# 07_LMS7002M_Power.net
KiCad netlist of a schematic drawn in Altium Designer
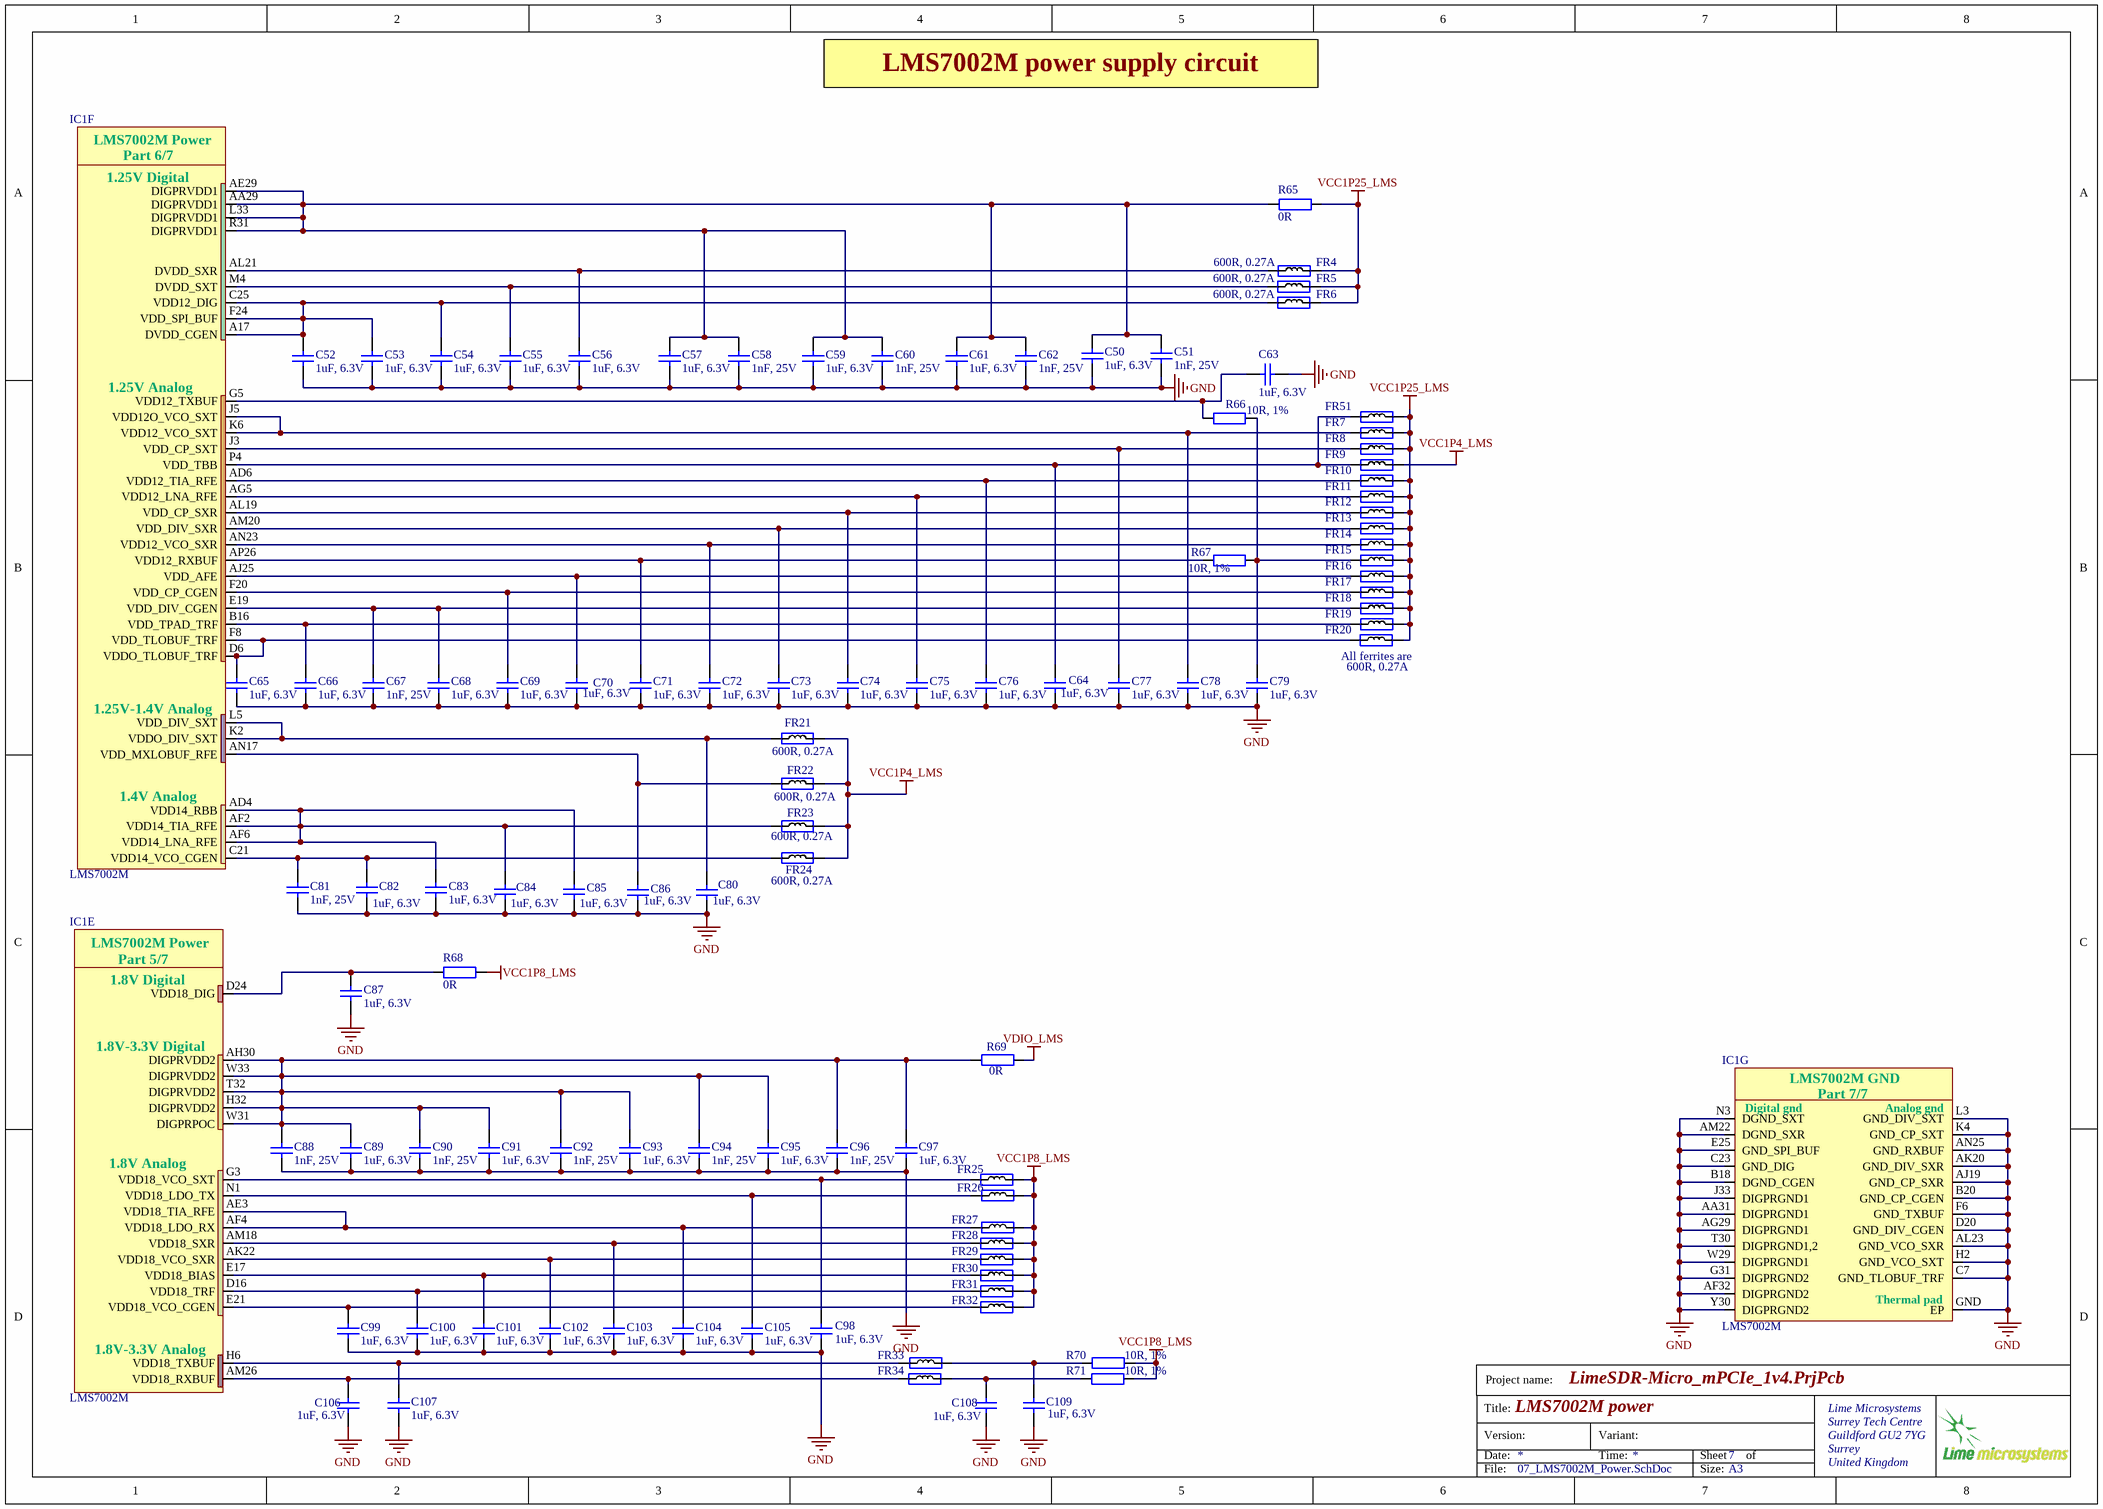
[diagram p0: 07_LMS7002M_Power.SchDoc]

(export (version "E")
  (design (tool "Eeschema 10.0.6"))
  (components
    (comp (ref "C50")
      (value "1uF, 6.3V")
      (footprint "CAP0201")
      (fields (field (name "TOLERANCE") "±20%") (field (name "MANUFACTURER") "TDK Corporation"))
      (libsource (lib "LimeMicroAltiumLib_schLib") (part "Cap_0402"))
    )
    (comp (ref "C51")
      (value "1nF, 25V")
      (footprint "CAP0201")
      (fields (field (name "TOLERANCE") "±10%") (field (name "MANUFACTURER") "TDK Corporation"))
      (libsource (lib "LimeMicroAltiumLib_schLib") (part "Cap_0402"))
    )
    (comp (ref "C52")
      (value "1uF, 6.3V")
      (footprint "CAP0201")
      (fields (field (name "TOLERANCE") "±20%") (field (name "MANUFACTURER") "TDK Corporation"))
      (libsource (lib "LimeMicroAltiumLib_schLib") (part "Cap_0402"))
    )
    (comp (ref "C53")
      (value "1uF, 6.3V")
      (footprint "CAP0201")
      (fields (field (name "TOLERANCE") "±20%") (field (name "MANUFACTURER") "TDK Corporation"))
      (libsource (lib "LimeMicroAltiumLib_schLib") (part "Cap_0402"))
    )
    (comp (ref "C54")
      (value "1uF, 6.3V")
      (footprint "CAP0201")
      (fields (field (name "TOLERANCE") "±20%") (field (name "MANUFACTURER") "TDK Corporation"))
      (libsource (lib "LimeMicroAltiumLib_schLib") (part "Cap_0402"))
    )
    (comp (ref "C55")
      (value "1uF, 6.3V")
      (footprint "CAP0201")
      (fields (field (name "TOLERANCE") "±20%") (field (name "MANUFACTURER") "TDK Corporation"))
      (libsource (lib "LimeMicroAltiumLib_schLib") (part "Cap_0402"))
    )
    (comp (ref "C56")
      (value "1uF, 6.3V")
      (footprint "CAP0201")
      (fields (field (name "TOLERANCE") "±20%") (field (name "MANUFACTURER") "TDK Corporation"))
      (libsource (lib "LimeMicroAltiumLib_schLib") (part "Cap_0402"))
    )
    (comp (ref "C57")
      (value "1uF, 6.3V")
      (footprint "CAP0201")
      (fields (field (name "TOLERANCE") "±20%") (field (name "MANUFACTURER") "TDK Corporation"))
      (libsource (lib "LimeMicroAltiumLib_schLib") (part "Cap_0402"))
    )
    (comp (ref "C58")
      (value "1nF, 25V")
      (footprint "CAP0201")
      (fields (field (name "TOLERANCE") "±10%") (field (name "MANUFACTURER") "TDK Corporation"))
      (libsource (lib "LimeMicroAltiumLib_schLib") (part "Cap_0402"))
    )
    (comp (ref "C59")
      (value "1uF, 6.3V")
      (footprint "CAP0201")
      (fields (field (name "TOLERANCE") "±20%") (field (name "MANUFACTURER") "TDK Corporation"))
      (libsource (lib "LimeMicroAltiumLib_schLib") (part "Cap_0402"))
    )
    (comp (ref "C60")
      (value "1nF, 25V")
      (footprint "CAP0201")
      (fields (field (name "TOLERANCE") "±10%") (field (name "MANUFACTURER") "TDK Corporation"))
      (libsource (lib "LimeMicroAltiumLib_schLib") (part "Cap_0402"))
    )
    (comp (ref "C61")
      (value "1uF, 6.3V")
      (footprint "CAP0201")
      (fields (field (name "TOLERANCE") "±20%") (field (name "MANUFACTURER") "TDK Corporation"))
      (libsource (lib "LimeMicroAltiumLib_schLib") (part "Cap_0402"))
    )
    (comp (ref "C62")
      (value "1nF, 25V")
      (footprint "CAP0201")
      (fields (field (name "TOLERANCE") "±10%") (field (name "MANUFACTURER") "TDK Corporation"))
      (libsource (lib "LimeMicroAltiumLib_schLib") (part "Cap_0402"))
    )
    (comp (ref "C63")
      (value "1uF, 6.3V")
      (footprint "CAP0201")
      (fields (field (name "TOLERANCE") "±20%") (field (name "MANUFACTURER") "TDK Corporation"))
      (libsource (lib "LimeMicroAltiumLib_schLib") (part "Cap_0402"))
    )
    (comp (ref "C64")
      (value "1uF, 6.3V")
      (footprint "CAP0201")
      (fields (field (name "TOLERANCE") "±20%") (field (name "MANUFACTURER") "TDK Corporation"))
      (libsource (lib "LimeMicroAltiumLib_schLib") (part "Cap_0402"))
    )
    (comp (ref "C65")
      (value "1uF, 6.3V")
      (footprint "CAP0201")
      (fields (field (name "TOLERANCE") "±20%") (field (name "MANUFACTURER") "TDK Corporation"))
      (libsource (lib "LimeMicroAltiumLib_schLib") (part "Cap_0402"))
    )
    (comp (ref "C66")
      (value "1uF, 6.3V")
      (footprint "CAP0201")
      (fields (field (name "TOLERANCE") "±20%") (field (name "MANUFACTURER") "TDK Corporation"))
      (libsource (lib "LimeMicroAltiumLib_schLib") (part "Cap_0402"))
    )
    (comp (ref "C67")
      (value "1nF, 25V")
      (footprint "CAP0201")
      (fields (field (name "TOLERANCE") "±10%") (field (name "MANUFACTURER") "TDK Corporation"))
      (libsource (lib "LimeMicroAltiumLib_schLib") (part "Cap_0402"))
    )
    (comp (ref "C68")
      (value "1uF, 6.3V")
      (footprint "CAP0201")
      (fields (field (name "TOLERANCE") "±20%") (field (name "MANUFACTURER") "TDK Corporation"))
      (libsource (lib "LimeMicroAltiumLib_schLib") (part "Cap_0402"))
    )
    (comp (ref "C69")
      (value "1uF, 6.3V")
      (footprint "CAP0201")
      (fields (field (name "TOLERANCE") "±20%") (field (name "MANUFACTURER") "TDK Corporation"))
      (libsource (lib "LimeMicroAltiumLib_schLib") (part "Cap_0402"))
    )
    (comp (ref "C70")
      (value "1uF, 6.3V")
      (footprint "CAP0201")
      (fields (field (name "TOLERANCE") "±20%") (field (name "MANUFACTURER") "TDK Corporation"))
      (libsource (lib "LimeMicroAltiumLib_schLib") (part "Cap_0402"))
    )
    (comp (ref "C71")
      (value "1uF, 6.3V")
      (footprint "CAP0201")
      (fields (field (name "TOLERANCE") "±20%") (field (name "MANUFACTURER") "TDK Corporation"))
      (libsource (lib "LimeMicroAltiumLib_schLib") (part "Cap_0402"))
    )
    (comp (ref "C72")
      (value "1uF, 6.3V")
      (footprint "CAP0201")
      (fields (field (name "TOLERANCE") "±20%") (field (name "MANUFACTURER") "TDK Corporation"))
      (libsource (lib "LimeMicroAltiumLib_schLib") (part "Cap_0402"))
    )
    (comp (ref "C73")
      (value "1uF, 6.3V")
      (footprint "CAP0201")
      (fields (field (name "TOLERANCE") "±20%") (field (name "MANUFACTURER") "TDK Corporation"))
      (libsource (lib "LimeMicroAltiumLib_schLib") (part "Cap_0402"))
    )
    (comp (ref "C74")
      (value "1uF, 6.3V")
      (footprint "CAP0201")
      (fields (field (name "TOLERANCE") "±20%") (field (name "MANUFACTURER") "TDK Corporation"))
      (libsource (lib "LimeMicroAltiumLib_schLib") (part "Cap_0402"))
    )
    (comp (ref "C75")
      (value "1uF, 6.3V")
      (footprint "CAP0201")
      (fields (field (name "TOLERANCE") "±20%") (field (name "MANUFACTURER") "TDK Corporation"))
      (libsource (lib "LimeMicroAltiumLib_schLib") (part "Cap_0402"))
    )
    (comp (ref "C76")
      (value "1uF, 6.3V")
      (footprint "CAP0201")
      (fields (field (name "TOLERANCE") "±20%") (field (name "MANUFACTURER") "TDK Corporation"))
      (libsource (lib "LimeMicroAltiumLib_schLib") (part "Cap_0402"))
    )
    (comp (ref "C77")
      (value "1uF, 6.3V")
      (footprint "CAP0201")
      (fields (field (name "TOLERANCE") "±20%") (field (name "MANUFACTURER") "TDK Corporation"))
      (libsource (lib "LimeMicroAltiumLib_schLib") (part "Cap_0402"))
    )
    (comp (ref "C78")
      (value "1uF, 6.3V")
      (footprint "CAP0201")
      (fields (field (name "TOLERANCE") "±20%") (field (name "MANUFACTURER") "TDK Corporation"))
      (libsource (lib "LimeMicroAltiumLib_schLib") (part "Cap_0402"))
    )
    (comp (ref "C79")
      (value "1uF, 6.3V")
      (footprint "CAP0201")
      (fields (field (name "TOLERANCE") "±20%") (field (name "MANUFACTURER") "TDK Corporation"))
      (libsource (lib "LimeMicroAltiumLib_schLib") (part "Cap_0402"))
    )
    (comp (ref "C80")
      (value "1uF, 6.3V")
      (footprint "CAP0201")
      (fields (field (name "TOLERANCE") "±20%") (field (name "MANUFACTURER") "TDK Corporation"))
      (libsource (lib "LimeMicroAltiumLib_schLib") (part "Cap_0402"))
    )
    (comp (ref "C81")
      (value "1nF, 25V")
      (footprint "CAP0201")
      (fields (field (name "TOLERANCE") "±10%") (field (name "MANUFACTURER") "TDK Corporation"))
      (libsource (lib "LimeMicroAltiumLib_schLib") (part "Cap_0402"))
    )
    (comp (ref "C82")
      (value "1uF, 6.3V")
      (footprint "CAP0201")
      (fields (field (name "TOLERANCE") "±20%") (field (name "MANUFACTURER") "TDK Corporation"))
      (libsource (lib "LimeMicroAltiumLib_schLib") (part "Cap_0402"))
    )
    (comp (ref "C83")
      (value "1uF, 6.3V")
      (footprint "CAP0201")
      (fields (field (name "TOLERANCE") "±20%") (field (name "MANUFACTURER") "TDK Corporation"))
      (libsource (lib "LimeMicroAltiumLib_schLib") (part "Cap_0402"))
    )
    (comp (ref "C84")
      (value "1uF, 6.3V")
      (footprint "CAP0201")
      (fields (field (name "TOLERANCE") "±20%") (field (name "MANUFACTURER") "TDK Corporation"))
      (libsource (lib "LimeMicroAltiumLib_schLib") (part "Cap_0402"))
    )
    (comp (ref "C85")
      (value "1uF, 6.3V")
      (footprint "CAP0201")
      (fields (field (name "TOLERANCE") "±20%") (field (name "MANUFACTURER") "TDK Corporation"))
      (libsource (lib "LimeMicroAltiumLib_schLib") (part "Cap_0402"))
    )
    (comp (ref "C86")
      (value "1uF, 6.3V")
      (footprint "CAP0201")
      (fields (field (name "TOLERANCE") "±20%") (field (name "MANUFACTURER") "TDK Corporation"))
      (libsource (lib "LimeMicroAltiumLib_schLib") (part "Cap_0402"))
    )
    (comp (ref "C87")
      (value "1uF, 6.3V")
      (footprint "CAP0201")
      (fields (field (name "TOLERANCE") "±20%") (field (name "MANUFACTURER") "TDK Corporation"))
      (libsource (lib "LimeMicroAltiumLib_schLib") (part "Cap_0402"))
    )
    (comp (ref "C88")
      (value "1nF, 25V")
      (footprint "CAP0201")
      (fields (field (name "TOLERANCE") "±10%") (field (name "MANUFACTURER") "TDK Corporation"))
      (libsource (lib "LimeMicroAltiumLib_schLib") (part "Cap_0402"))
    )
    (comp (ref "C89")
      (value "1uF, 6.3V")
      (footprint "CAP0201")
      (fields (field (name "TOLERANCE") "±20%") (field (name "MANUFACTURER") "TDK Corporation"))
      (libsource (lib "LimeMicroAltiumLib_schLib") (part "Cap_0402"))
    )
    (comp (ref "C90")
      (value "1nF, 25V")
      (footprint "CAP0201")
      (fields (field (name "TOLERANCE") "±10%") (field (name "MANUFACTURER") "TDK Corporation"))
      (libsource (lib "LimeMicroAltiumLib_schLib") (part "Cap_0402"))
    )
    (comp (ref "C91")
      (value "1uF, 6.3V")
      (footprint "CAP0201")
      (fields (field (name "TOLERANCE") "±20%") (field (name "MANUFACTURER") "TDK Corporation"))
      (libsource (lib "LimeMicroAltiumLib_schLib") (part "Cap_0402"))
    )
    (comp (ref "C92")
      (value "1nF, 25V")
      (footprint "CAP0201")
      (fields (field (name "TOLERANCE") "±10%") (field (name "MANUFACTURER") "TDK Corporation"))
      (libsource (lib "LimeMicroAltiumLib_schLib") (part "Cap_0402"))
    )
    (comp (ref "C93")
      (value "1uF, 6.3V")
      (footprint "CAP0201")
      (fields (field (name "TOLERANCE") "±20%") (field (name "MANUFACTURER") "TDK Corporation"))
      (libsource (lib "LimeMicroAltiumLib_schLib") (part "Cap_0402"))
    )
    (comp (ref "C94")
      (value "1nF, 25V")
      (footprint "CAP0201")
      (fields (field (name "TOLERANCE") "±10%") (field (name "MANUFACTURER") "TDK Corporation"))
      (libsource (lib "LimeMicroAltiumLib_schLib") (part "Cap_0402"))
    )
    (comp (ref "C95")
      (value "1uF, 6.3V")
      (footprint "CAP0201")
      (fields (field (name "TOLERANCE") "±20%") (field (name "MANUFACTURER") "TDK Corporation"))
      (libsource (lib "LimeMicroAltiumLib_schLib") (part "Cap_0402"))
    )
    (comp (ref "C96")
      (value "1nF, 25V")
      (footprint "CAP0201")
      (fields (field (name "TOLERANCE") "±10%") (field (name "MANUFACTURER") "TDK Corporation"))
      (libsource (lib "LimeMicroAltiumLib_schLib") (part "Cap_0402"))
    )
    (comp (ref "C97")
      (value "1uF, 6.3V")
      (footprint "CAP0201")
      (fields (field (name "TOLERANCE") "±20%") (field (name "MANUFACTURER") "TDK Corporation"))
      (libsource (lib "LimeMicroAltiumLib_schLib") (part "Cap_0402"))
    )
    (comp (ref "C98")
      (value "1uF, 6.3V")
      (footprint "CAP0201")
      (fields (field (name "TOLERANCE") "±20%") (field (name "MANUFACTURER") "TDK Corporation"))
      (libsource (lib "LimeMicroAltiumLib_schLib") (part "Cap_0402"))
    )
    (comp (ref "C99")
      (value "1uF, 6.3V")
      (footprint "CAP0201")
      (fields (field (name "TOLERANCE") "±20%") (field (name "MANUFACTURER") "TDK Corporation"))
      (libsource (lib "LimeMicroAltiumLib_schLib") (part "Cap_0402"))
    )
    (comp (ref "C100")
      (value "1uF, 6.3V")
      (footprint "CAP0201")
      (fields (field (name "TOLERANCE") "±20%") (field (name "MANUFACTURER") "TDK Corporation"))
      (libsource (lib "LimeMicroAltiumLib_schLib") (part "Cap_0402"))
    )
    (comp (ref "C101")
      (value "1uF, 6.3V")
      (footprint "CAP0201")
      (fields (field (name "TOLERANCE") "±20%") (field (name "MANUFACTURER") "TDK Corporation"))
      (libsource (lib "LimeMicroAltiumLib_schLib") (part "Cap_0402"))
    )
    (comp (ref "C102")
      (value "1uF, 6.3V")
      (footprint "CAP0201")
      (fields (field (name "TOLERANCE") "±20%") (field (name "MANUFACTURER") "TDK Corporation"))
      (libsource (lib "LimeMicroAltiumLib_schLib") (part "Cap_0402"))
    )
    (comp (ref "C103")
      (value "1uF, 6.3V")
      (footprint "CAP0201")
      (fields (field (name "TOLERANCE") "±20%") (field (name "MANUFACTURER") "TDK Corporation"))
      (libsource (lib "LimeMicroAltiumLib_schLib") (part "Cap_0402"))
    )
    (comp (ref "C104")
      (value "1uF, 6.3V")
      (footprint "CAP0201")
      (fields (field (name "TOLERANCE") "±20%") (field (name "MANUFACTURER") "TDK Corporation"))
      (libsource (lib "LimeMicroAltiumLib_schLib") (part "Cap_0402"))
    )
    (comp (ref "C105")
      (value "1uF, 6.3V")
      (footprint "CAP0201")
      (fields (field (name "TOLERANCE") "±20%") (field (name "MANUFACTURER") "TDK Corporation"))
      (libsource (lib "LimeMicroAltiumLib_schLib") (part "Cap_0402"))
    )
    (comp (ref "C106")
      (value "1uF, 6.3V")
      (footprint "CAP0201")
      (fields (field (name "TOLERANCE") "±20%") (field (name "MANUFACTURER") "TDK Corporation"))
      (libsource (lib "LimeMicroAltiumLib_schLib") (part "Cap_0402"))
    )
    (comp (ref "C107")
      (value "1uF, 6.3V")
      (footprint "CAP0201")
      (fields (field (name "TOLERANCE") "±20%") (field (name "MANUFACTURER") "TDK Corporation"))
      (libsource (lib "LimeMicroAltiumLib_schLib") (part "Cap_0402"))
    )
    (comp (ref "C108")
      (value "1uF, 6.3V")
      (footprint "CAP0201")
      (fields (field (name "TOLERANCE") "±20%") (field (name "MANUFACTURER") "TDK Corporation"))
      (libsource (lib "LimeMicroAltiumLib_schLib") (part "Cap_0402"))
    )
    (comp (ref "C109")
      (value "1uF, 6.3V")
      (footprint "CAP0201")
      (fields (field (name "TOLERANCE") "±20%") (field (name "MANUFACTURER") "TDK Corporation"))
      (libsource (lib "LimeMicroAltiumLib_schLib") (part "Cap_0402"))
    )
    (comp (ref "FR4")
      (value "600R, 0.27A")
      (footprint "RES0201")
      (fields (field (name "MANUFACTURER") "Taiyo Yuden"))
      (libsource (lib "LimeMicroAltiumLib_schLib") (part "Ferrite"))
    )
    (comp (ref "FR5")
      (value "600R, 0.27A")
      (footprint "RES0201")
      (fields (field (name "MANUFACTURER") "Taiyo Yuden"))
      (libsource (lib "LimeMicroAltiumLib_schLib") (part "Ferrite"))
    )
    (comp (ref "FR6")
      (value "600R, 0.27A")
      (footprint "RES0201")
      (fields (field (name "MANUFACTURER") "Taiyo Yuden"))
      (libsource (lib "LimeMicroAltiumLib_schLib") (part "Ferrite"))
    )
    (comp (ref "FR7")
      (value "600R, 0.27A")
      (footprint "RES0201")
      (fields (field (name "MANUFACTURER") "Taiyo Yuden"))
      (libsource (lib "LimeMicroAltiumLib_schLib") (part "Ferrite"))
    )
    (comp (ref "FR8")
      (value "600R, 0.27A")
      (footprint "RES0201")
      (fields (field (name "MANUFACTURER") "Taiyo Yuden"))
      (libsource (lib "LimeMicroAltiumLib_schLib") (part "Ferrite"))
    )
    (comp (ref "FR9")
      (value "600R, 0.27A")
      (footprint "RES0201")
      (fields (field (name "MANUFACTURER") "Taiyo Yuden"))
      (libsource (lib "LimeMicroAltiumLib_schLib") (part "Ferrite"))
    )
    (comp (ref "FR10")
      (value "600R, 0.27A")
      (footprint "RES0201")
      (fields (field (name "MANUFACTURER") "Taiyo Yuden"))
      (libsource (lib "LimeMicroAltiumLib_schLib") (part "Ferrite"))
    )
    (comp (ref "FR11")
      (value "600R, 0.27A")
      (footprint "RES0201")
      (fields (field (name "MANUFACTURER") "Taiyo Yuden"))
      (libsource (lib "LimeMicroAltiumLib_schLib") (part "Ferrite"))
    )
    (comp (ref "FR12")
      (value "600R, 0.27A")
      (footprint "RES0201")
      (fields (field (name "MANUFACTURER") "Taiyo Yuden"))
      (libsource (lib "LimeMicroAltiumLib_schLib") (part "Ferrite"))
    )
    (comp (ref "FR13")
      (value "600R, 0.27A")
      (footprint "RES0201")
      (fields (field (name "MANUFACTURER") "Taiyo Yuden"))
      (libsource (lib "LimeMicroAltiumLib_schLib") (part "Ferrite"))
    )
    (comp (ref "FR14")
      (value "600R, 0.27A")
      (footprint "RES0201")
      (fields (field (name "MANUFACTURER") "Taiyo Yuden"))
      (libsource (lib "LimeMicroAltiumLib_schLib") (part "Ferrite"))
    )
    (comp (ref "FR15")
      (value "600R, 0.27A")
      (footprint "RES0201")
      (fields (field (name "MANUFACTURER") "Taiyo Yuden"))
      (libsource (lib "LimeMicroAltiumLib_schLib") (part "Ferrite"))
    )
    (comp (ref "FR16")
      (value "600R, 0.27A")
      (footprint "RES0201")
      (fields (field (name "MANUFACTURER") "Taiyo Yuden"))
      (libsource (lib "LimeMicroAltiumLib_schLib") (part "Ferrite"))
    )
    (comp (ref "FR17")
      (value "600R, 0.27A")
      (footprint "RES0201")
      (fields (field (name "MANUFACTURER") "Taiyo Yuden"))
      (libsource (lib "LimeMicroAltiumLib_schLib") (part "Ferrite"))
    )
    (comp (ref "FR18")
      (value "600R, 0.27A")
      (footprint "RES0201")
      (fields (field (name "MANUFACTURER") "Taiyo Yuden"))
      (libsource (lib "LimeMicroAltiumLib_schLib") (part "Ferrite"))
    )
    (comp (ref "FR19")
      (value "600R, 0.27A")
      (footprint "RES0201")
      (fields (field (name "MANUFACTURER") "Taiyo Yuden"))
      (libsource (lib "LimeMicroAltiumLib_schLib") (part "Ferrite"))
    )
    (comp (ref "FR20")
      (value "600R, 0.27A")
      (footprint "RES0201")
      (fields (field (name "MANUFACTURER") "Taiyo Yuden"))
      (libsource (lib "LimeMicroAltiumLib_schLib") (part "Ferrite"))
    )
    (comp (ref "FR21")
      (value "600R, 0.27A")
      (footprint "RES0201")
      (fields (field (name "MANUFACTURER") "Taiyo Yuden"))
      (libsource (lib "LimeMicroAltiumLib_schLib") (part "Ferrite"))
    )
    (comp (ref "FR22")
      (value "600R, 0.27A")
      (footprint "RES0201")
      (fields (field (name "MANUFACTURER") "Taiyo Yuden"))
      (libsource (lib "LimeMicroAltiumLib_schLib") (part "Ferrite"))
    )
    (comp (ref "FR23")
      (value "600R, 0.27A")
      (footprint "RES0201")
      (fields (field (name "MANUFACTURER") "Taiyo Yuden"))
      (libsource (lib "LimeMicroAltiumLib_schLib") (part "Ferrite"))
    )
    (comp (ref "FR24")
      (value "600R, 0.27A")
      (footprint "RES0201")
      (fields (field (name "MANUFACTURER") "Taiyo Yuden"))
      (libsource (lib "LimeMicroAltiumLib_schLib") (part "Ferrite"))
    )
    (comp (ref "FR25")
      (value "600R, 0.27A")
      (footprint "RES0201")
      (fields (field (name "MANUFACTURER") "Taiyo Yuden"))
      (libsource (lib "LimeMicroAltiumLib_schLib") (part "Ferrite"))
    )
    (comp (ref "FR26")
      (value "600R, 0.27A")
      (footprint "RES0201")
      (fields (field (name "MANUFACTURER") "Taiyo Yuden"))
      (libsource (lib "") (part "Ferrite_1"))
    )
    (comp (ref "FR27")
      (value "600R, 0.27A")
      (footprint "RES0201")
      (fields (field (name "MANUFACTURER") "Taiyo Yuden"))
      (libsource (lib "") (part "Ferrite_1"))
    )
    (comp (ref "FR28")
      (value "600R, 0.27A")
      (footprint "RES0201")
      (fields (field (name "MANUFACTURER") "Taiyo Yuden"))
      (libsource (lib "LimeMicroAltiumLib_schLib") (part "Ferrite"))
    )
    (comp (ref "FR29")
      (value "600R, 0.27A")
      (footprint "RES0201")
      (fields (field (name "MANUFACTURER") "Taiyo Yuden"))
      (libsource (lib "LimeMicroAltiumLib_schLib") (part "Ferrite"))
    )
    (comp (ref "FR30")
      (value "600R, 0.27A")
      (footprint "RES0201")
      (fields (field (name "MANUFACTURER") "Taiyo Yuden"))
      (libsource (lib "LimeMicroAltiumLib_schLib") (part "Ferrite"))
    )
    (comp (ref "FR31")
      (value "600R, 0.27A")
      (footprint "RES0201")
      (fields (field (name "MANUFACTURER") "Taiyo Yuden"))
      (libsource (lib "LimeMicroAltiumLib_schLib") (part "Ferrite"))
    )
    (comp (ref "FR32")
      (value "600R, 0.27A")
      (footprint "RES0201")
      (fields (field (name "MANUFACTURER") "Taiyo Yuden"))
      (libsource (lib "LimeMicroAltiumLib_schLib") (part "Ferrite"))
    )
    (comp (ref "FR33")
      (value "600R, 0.27A")
      (footprint "RES0201")
      (fields (field (name "MANUFACTURER") "Taiyo Yuden"))
      (libsource (lib "") (part "Ferrite_1"))
    )
    (comp (ref "FR34")
      (value "600R, 0.27A")
      (footprint "RES0201")
      (fields (field (name "MANUFACTURER") "Taiyo Yuden"))
      (libsource (lib "LimeMicroAltiumLib_schLib") (part "Ferrite"))
    )
    (comp (ref "FR51")
      (value "600R, 0.27A")
      (footprint "RES0201")
      (fields (field (name "MANUFACTURER") "Taiyo Yuden"))
      (libsource (lib "LimeMicroAltiumLib_schLib") (part "Ferrite"))
    )
    (comp (ref "IC1")
      (value "LMS7002M")
      (footprint "LMS7002M_v5_LESS_SILK")
      (description "Schematic symbol revision 4. Default footprint - 0.31mm pad")
      (fields (field (name "MANUFACTURER") "Lime Microsystems"))
      (libsource (lib "LimeMicroAltiumLib_schLib_r04") (part "LMS7002Mr4"))
    )
    (comp (ref "R65")
      (value "0R")
      (footprint "RES0402")
      (fields (field (name "MANUFACTURER") "Yageo") (field (name "TOLERANCE") "Jumper"))
      (libsource (lib "LimeMicroAltiumLib_schLib") (part "Res_0402"))
    )
    (comp (ref "R66")
      (value "10R, 1%")
      (footprint "RES0201")
      (fields
        (field (name "MANUFACTURER") "Panasonic Electronic Components")
        (field (name "TOLERANCE") "±1%")
      )
      (libsource (lib "LimeMicroAltiumLib_schLib") (part "Res_0402"))
    )
    (comp (ref "R67")
      (value "10R, 1%")
      (footprint "RES0201")
      (fields
        (field (name "MANUFACTURER") "Panasonic Electronic Components")
        (field (name "TOLERANCE") "±1%")
      )
      (libsource (lib "LimeMicroAltiumLib_schLib") (part "Res_0402"))
    )
    (comp (ref "R68")
      (value "0R")
      (footprint "RES0201")
      (fields (field (name "MANUFACTURER") "Yageo") (field (name "TOLERANCE") "5%"))
      (libsource (lib "LimeMicroAltiumLib_schLib") (part "Res_0402"))
    )
    (comp (ref "R69")
      (value "0R")
      (footprint "RES0402")
      (fields (field (name "MANUFACTURER") "Yageo") (field (name "TOLERANCE") "Jumper"))
      (libsource (lib "LimeMicroAltiumLib_schLib") (part "Res_0402"))
    )
    (comp (ref "R70")
      (value "10R, 1%")
      (footprint "RES0201")
      (fields
        (field (name "MANUFACTURER") "Panasonic Electronic Components")
        (field (name "TOLERANCE") "±1%")
      )
      (libsource (lib "LimeMicroAltiumLib_schLib") (part "Res_0402"))
    )
    (comp (ref "R71")
      (value "10R, 1%")
      (footprint "RES0201")
      (fields
        (field (name "MANUFACTURER") "Panasonic Electronic Components")
        (field (name "TOLERANCE") "±1%")
      )
      (libsource (lib "LimeMicroAltiumLib_schLib") (part "Res_0402"))
    )
  )
  (nets
    (net (code "1") (name "GND") (class "Default")
      (node (ref "C100") (pin "2") (pinfunction "2_2") (pintype "passive"))
      (node (ref "C101") (pin "2") (pinfunction "2_2") (pintype "passive"))
      (node (ref "C102") (pin "2") (pinfunction "2_2") (pintype "passive"))
      (node (ref "C103") (pin "2") (pinfunction "2_2") (pintype "passive"))
      (node (ref "C104") (pin "2") (pinfunction "2_2") (pintype "passive"))
      (node (ref "C105") (pin "2") (pinfunction "2_2") (pintype "passive"))
      (node (ref "C106") (pin "2") (pinfunction "2_2") (pintype "passive"))
      (node (ref "C107") (pin "2") (pinfunction "2_2") (pintype "passive"))
      (node (ref "C108") (pin "2") (pinfunction "2_2") (pintype "passive"))
      (node (ref "C109") (pin "2") (pinfunction "2_2") (pintype "passive"))
      (node (ref "C50") (pin "2") (pinfunction "2_2") (pintype "passive"))
      (node (ref "C51") (pin "2") (pinfunction "2_2") (pintype "passive"))
      (node (ref "C52") (pin "2") (pinfunction "2_2") (pintype "passive"))
      (node (ref "C53") (pin "2") (pinfunction "2_2") (pintype "passive"))
      (node (ref "C54") (pin "2") (pinfunction "2_2") (pintype "passive"))
      (node (ref "C55") (pin "1") (pinfunction "1_1") (pintype "passive"))
      (node (ref "C56") (pin "2") (pinfunction "2_2") (pintype "passive"))
      (node (ref "C57") (pin "2") (pinfunction "2_2") (pintype "passive"))
      (node (ref "C58") (pin "2") (pinfunction "2_2") (pintype "passive"))
      (node (ref "C59") (pin "2") (pinfunction "2_2") (pintype "passive"))
      (node (ref "C60") (pin "2") (pinfunction "2_2") (pintype "passive"))
      (node (ref "C61") (pin "2") (pinfunction "2_2") (pintype "passive"))
      (node (ref "C62") (pin "2") (pinfunction "2_2") (pintype "passive"))
      (node (ref "C63") (pin "2") (pinfunction "2_2") (pintype "passive"))
      (node (ref "C64") (pin "2") (pinfunction "2_2") (pintype "passive"))
      (node (ref "C65") (pin "2") (pinfunction "2_2") (pintype "passive"))
      (node (ref "C66") (pin "2") (pinfunction "2_2") (pintype "passive"))
      (node (ref "C67") (pin "2") (pinfunction "2_2") (pintype "passive"))
      (node (ref "C68") (pin "2") (pinfunction "2_2") (pintype "passive"))
      (node (ref "C69") (pin "1") (pinfunction "1_1") (pintype "passive"))
      (node (ref "C70") (pin "2") (pinfunction "2_2") (pintype "passive"))
      (node (ref "C71") (pin "2") (pinfunction "2_2") (pintype "passive"))
      (node (ref "C72") (pin "2") (pinfunction "2_2") (pintype "passive"))
      (node (ref "C73") (pin "2") (pinfunction "2_2") (pintype "passive"))
      (node (ref "C74") (pin "2") (pinfunction "2_2") (pintype "passive"))
      (node (ref "C75") (pin "2") (pinfunction "2_2") (pintype "passive"))
      (node (ref "C76") (pin "1") (pinfunction "1_1") (pintype "passive"))
      (node (ref "C77") (pin "2") (pinfunction "2_2") (pintype "passive"))
      (node (ref "C78") (pin "1") (pinfunction "1_1") (pintype "passive"))
      (node (ref "C79") (pin "1") (pinfunction "1_1") (pintype "passive"))
      (node (ref "C80") (pin "2") (pinfunction "2_2") (pintype "passive"))
      (node (ref "C81") (pin "2") (pinfunction "2_2") (pintype "passive"))
      (node (ref "C82") (pin "2") (pinfunction "2_2") (pintype "passive"))
      (node (ref "C83") (pin "2") (pinfunction "2_2") (pintype "passive"))
      (node (ref "C84") (pin "2") (pinfunction "2_2") (pintype "passive"))
      (node (ref "C85") (pin "2") (pinfunction "2_2") (pintype "passive"))
      (node (ref "C86") (pin "2") (pinfunction "2_2") (pintype "passive"))
      (node (ref "C87") (pin "2") (pinfunction "2_2") (pintype "passive"))
      (node (ref "C88") (pin "2") (pinfunction "2_2") (pintype "passive"))
      (node (ref "C89") (pin "2") (pinfunction "2_2") (pintype "passive"))
      (node (ref "C90") (pin "2") (pinfunction "2_2") (pintype "passive"))
      (node (ref "C91") (pin "2") (pinfunction "2_2") (pintype "passive"))
      (node (ref "C92") (pin "2") (pinfunction "2_2") (pintype "passive"))
      (node (ref "C93") (pin "2") (pinfunction "2_2") (pintype "passive"))
      (node (ref "C94") (pin "2") (pinfunction "2_2") (pintype "passive"))
      (node (ref "C95") (pin "2") (pinfunction "2_2") (pintype "passive"))
      (node (ref "C96") (pin "2") (pinfunction "2_2") (pintype "passive"))
      (node (ref "C97") (pin "2") (pinfunction "2_2") (pintype "passive"))
      (node (ref "C98") (pin "2") (pinfunction "2_2") (pintype "passive"))
      (node (ref "C99") (pin "2") (pinfunction "2_2") (pintype "passive"))
      (node (ref "IC1") (pin "AA31") (pinfunction "DIGPRGND1_AA31") (pintype "passive"))
      (node (ref "IC1") (pin "AF32") (pinfunction "DIGPRGND2_AF32") (pintype "passive"))
      (node (ref "IC1") (pin "AG29") (pinfunction "DIGPRGND1_AG29") (pintype "passive"))
      (node (ref "IC1") (pin "AJ19") (pinfunction "GND_CP_SXR_AJ19") (pintype "passive"))
      (node (ref "IC1") (pin "AK20") (pinfunction "GND_DIV_SXR_AK20") (pintype "passive"))
      (node (ref "IC1") (pin "AL23") (pinfunction "GND_VCO_SXR_AL23") (pintype "passive"))
      (node (ref "IC1") (pin "AM22") (pinfunction "DGND_SXR_AM22") (pintype "passive"))
      (node (ref "IC1") (pin "AN25") (pinfunction "GND_RXBUF_AN25") (pintype "passive"))
      (node (ref "IC1") (pin "B18") (pinfunction "DGND_CGEN_B18") (pintype "passive"))
      (node (ref "IC1") (pin "B20") (pinfunction "GND_CP_CGEN_B20") (pintype "passive"))
      (node (ref "IC1") (pin "C23") (pinfunction "GND_DIG_C23") (pintype "passive"))
      (node (ref "IC1") (pin "C7") (pinfunction "GND_TLOBUF_TRF_C7") (pintype "passive"))
      (node (ref "IC1") (pin "D20") (pinfunction "GND_DIV_CGEN_D20") (pintype "passive"))
      (node (ref "IC1") (pin "E25") (pinfunction "GND_SPI_BUF_E25") (pintype "passive"))
      (node (ref "IC1") (pin "F6") (pinfunction "GND_TXBUF_F6") (pintype "passive"))
      (node (ref "IC1") (pin "G31") (pinfunction "DIGPRGND2_G31") (pintype "passive"))
      (node (ref "IC1") (pin "GND") (pinfunction "EP_GND") (pintype "passive"))
      (node (ref "IC1") (pin "H2") (pinfunction "GND_VCO_SXT_H2") (pintype "passive"))
      (node (ref "IC1") (pin "J33") (pinfunction "DIGPRGND1_J33") (pintype "passive"))
      (node (ref "IC1") (pin "K4") (pinfunction "GND_CP_SXT_K4") (pintype "passive"))
      (node (ref "IC1") (pin "L3") (pinfunction "GND_DIV_SXT_L3") (pintype "passive"))
      (node (ref "IC1") (pin "N3") (pinfunction "DGND_SXT_N3") (pintype "passive"))
      (node (ref "IC1") (pin "T30") (pinfunction "DIGPRGND1,2_T30") (pintype "passive"))
      (node (ref "IC1") (pin "W29") (pinfunction "DIGPRGND1_W29") (pintype "passive"))
      (node (ref "IC1") (pin "Y30") (pinfunction "DIGPRGND2_Y30") (pintype "passive"))
    )
    (net (code "2") (name "Net-(C50-Pad1)") (class "Default")
      (node (ref "C50") (pin "1") (pinfunction "1_1") (pintype "passive"))
      (node (ref "C51") (pin "1") (pinfunction "1_1") (pintype "passive"))
      (node (ref "C57") (pin "1") (pinfunction "1_1") (pintype "passive"))
      (node (ref "C58") (pin "1") (pinfunction "1_1") (pintype "passive"))
      (node (ref "C59") (pin "1") (pinfunction "1_1") (pintype "passive"))
      (node (ref "C60") (pin "1") (pinfunction "1_1") (pintype "passive"))
      (node (ref "C61") (pin "1") (pinfunction "1_1") (pintype "passive"))
      (node (ref "C62") (pin "1") (pinfunction "1_1") (pintype "passive"))
      (node (ref "IC1") (pin "AA29") (pinfunction "DIGPRVDD1_AA29") (pintype "power_in"))
      (node (ref "IC1") (pin "AE29") (pinfunction "DIGPRVDD1_AE29") (pintype "power_in"))
      (node (ref "IC1") (pin "L33") (pinfunction "DIGPRVDD1_L33") (pintype "power_in"))
      (node (ref "IC1") (pin "R31") (pinfunction "DIGPRVDD1_R31") (pintype "power_in"))
      (node (ref "R65") (pin "2") (pinfunction "2_2") (pintype "passive"))
    )
    (net (code "3") (name "Net-(C79-Pad2)") (class "Default")
      (node (ref "C79") (pin "2") (pinfunction "2_2") (pintype "passive"))
      (node (ref "FR15") (pin "1") (pinfunction "1_1") (pintype "passive"))
      (node (ref "R66") (pin "2") (pinfunction "2_2") (pintype "passive"))
      (node (ref "R67") (pin "2") (pinfunction "2_2") (pintype "passive"))
    )
    (net (code "4") (name "Net-(C108-Pad1)") (class "Default")
      (node (ref "C108") (pin "1") (pinfunction "1_1") (pintype "passive"))
      (node (ref "FR34") (pin "2") (pinfunction "2_2") (pintype "passive"))
      (node (ref "R71") (pin "2") (pinfunction "2_2") (pintype "passive"))
    )
    (net (code "5") (name "Net-(C109-Pad1)") (class "Default")
      (node (ref "C109") (pin "1") (pinfunction "1_1") (pintype "passive"))
      (node (ref "FR33") (pin "1") (pinfunction "1_1") (pintype "passive"))
      (node (ref "R70") (pin "1") (pinfunction "1_1") (pintype "passive"))
    )
    (net (code "6") (name "Net-(IC1E-DIGPRPOC)") (class "Default")
      (node (ref "C88") (pin "1") (pinfunction "1_1") (pintype "passive"))
      (node (ref "C89") (pin "1") (pinfunction "1_1") (pintype "passive"))
      (node (ref "C90") (pin "1") (pinfunction "1_1") (pintype "passive"))
      (node (ref "C91") (pin "1") (pinfunction "1_1") (pintype "passive"))
      (node (ref "C92") (pin "1") (pinfunction "1_1") (pintype "passive"))
      (node (ref "C93") (pin "1") (pinfunction "1_1") (pintype "passive"))
      (node (ref "C94") (pin "1") (pinfunction "1_1") (pintype "passive"))
      (node (ref "C95") (pin "1") (pinfunction "1_1") (pintype "passive"))
      (node (ref "C96") (pin "1") (pinfunction "1_1") (pintype "passive"))
      (node (ref "C97") (pin "1") (pinfunction "1_1") (pintype "passive"))
      (node (ref "IC1") (pin "AH30") (pinfunction "DIGPRVDD2_AH30") (pintype "power_in"))
      (node (ref "IC1") (pin "H32") (pinfunction "DIGPRVDD2_H32") (pintype "power_in"))
      (node (ref "IC1") (pin "T32") (pinfunction "DIGPRVDD2_T32") (pintype "power_in"))
      (node (ref "IC1") (pin "W31") (pinfunction "DIGPRPOC_W31") (pintype "power_in"))
      (node (ref "IC1") (pin "W33") (pinfunction "DIGPRVDD2_W33") (pintype "power_in"))
      (node (ref "R69") (pin "2") (pinfunction "2_2") (pintype "passive"))
    )
    (net (code "7") (name "Net-(IC1E-VDD18_BIAS)") (class "Default")
      (node (ref "C101") (pin "1") (pinfunction "1_1") (pintype "passive"))
      (node (ref "FR30") (pin "1") (pinfunction "1_1") (pintype "passive"))
      (node (ref "IC1") (pin "E17") (pinfunction "VDD18_BIAS_E17") (pintype "power_in"))
    )
    (net (code "8") (name "Net-(IC1E-VDD18_DIG)") (class "Default")
      (node (ref "C87") (pin "1") (pinfunction "1_1") (pintype "passive"))
      (node (ref "IC1") (pin "D24") (pinfunction "VDD18_DIG_D24") (pintype "power_in"))
      (node (ref "R68") (pin "1") (pinfunction "1_1") (pintype "passive"))
    )
    (net (code "9") (name "Net-(IC1E-VDD18_LDO_RX)") (class "Default")
      (node (ref "C104") (pin "1") (pinfunction "1_1") (pintype "passive"))
      (node (ref "FR27") (pin "2") (pinfunction "2_2") (pintype "passive"))
      (node (ref "IC1") (pin "AE3") (pinfunction "VDD18_TIA_RFE_AE3") (pintype "power_in"))
      (node (ref "IC1") (pin "AF4") (pinfunction "VDD18_LDO_RX_AF4") (pintype "power_in"))
    )
    (net (code "10") (name "Net-(IC1E-VDD18_LDO_TX)") (class "Default")
      (node (ref "C105") (pin "1") (pinfunction "1_1") (pintype "passive"))
      (node (ref "FR26") (pin "2") (pinfunction "2_2") (pintype "passive"))
      (node (ref "IC1") (pin "N1") (pinfunction "VDD18_LDO_TX_N1") (pintype "power_in"))
    )
    (net (code "11") (name "Net-(IC1E-VDD18_RXBUF)") (class "Default")
      (node (ref "C106") (pin "1") (pinfunction "1_1") (pintype "passive"))
      (node (ref "FR34") (pin "1") (pinfunction "1_1") (pintype "passive"))
      (node (ref "IC1") (pin "AM26") (pinfunction "VDD18_RXBUF_AM26") (pintype "power_in"))
    )
    (net (code "12") (name "Net-(IC1E-VDD18_SXR)") (class "Default")
      (node (ref "C103") (pin "1") (pinfunction "1_1") (pintype "passive"))
      (node (ref "FR28") (pin "1") (pinfunction "1_1") (pintype "passive"))
      (node (ref "IC1") (pin "AM18") (pinfunction "VDD18_SXR_AM18") (pintype "power_in"))
    )
    (net (code "13") (name "Net-(IC1E-VDD18_TRF)") (class "Default")
      (node (ref "C100") (pin "1") (pinfunction "1_1") (pintype "passive"))
      (node (ref "FR31") (pin "1") (pinfunction "1_1") (pintype "passive"))
      (node (ref "IC1") (pin "D16") (pinfunction "VDD18_TRF_D16") (pintype "power_in"))
    )
    (net (code "14") (name "Net-(IC1E-VDD18_TXBUF)") (class "Default")
      (node (ref "C107") (pin "1") (pinfunction "1_1") (pintype "passive"))
      (node (ref "FR33") (pin "2") (pinfunction "2_2") (pintype "passive"))
      (node (ref "IC1") (pin "H6") (pinfunction "VDD18_TXBUF_H6") (pintype "power_in"))
    )
    (net (code "15") (name "Net-(IC1E-VDD18_VCO_CGEN)") (class "Default")
      (node (ref "C99") (pin "1") (pinfunction "1_1") (pintype "passive"))
      (node (ref "FR32") (pin "1") (pinfunction "1_1") (pintype "passive"))
      (node (ref "IC1") (pin "E21") (pinfunction "VDD18_VCO_CGEN_E21") (pintype "power_in"))
    )
    (net (code "16") (name "Net-(IC1E-VDD18_VCO_SXR)") (class "Default")
      (node (ref "C102") (pin "1") (pinfunction "1_1") (pintype "passive"))
      (node (ref "FR29") (pin "1") (pinfunction "1_1") (pintype "passive"))
      (node (ref "IC1") (pin "AK22") (pinfunction "VDD18_VCO_SXR_AK22") (pintype "power_in"))
    )
    (net (code "17") (name "Net-(IC1E-VDD18_VCO_SXT)") (class "Default")
      (node (ref "C98") (pin "1") (pinfunction "1_1") (pintype "passive"))
      (node (ref "FR25") (pin "1") (pinfunction "1_1") (pintype "passive"))
      (node (ref "IC1") (pin "G3") (pinfunction "VDD18_VCO_SXT_G3") (pintype "power_in"))
    )
    (net (code "18") (name "Net-(IC1F-DVDD_CGEN)") (class "Default")
      (node (ref "C52") (pin "1") (pinfunction "1_1") (pintype "passive"))
      (node (ref "C53") (pin "1") (pinfunction "1_1") (pintype "passive"))
      (node (ref "C54") (pin "1") (pinfunction "1_1") (pintype "passive"))
      (node (ref "FR6") (pin "1") (pinfunction "1_1") (pintype "passive"))
      (node (ref "IC1") (pin "A17") (pinfunction "DVDD_CGEN_A17") (pintype "power_in"))
      (node (ref "IC1") (pin "C25") (pinfunction "VDD12_DIG_C25") (pintype "power_in"))
      (node (ref "IC1") (pin "F24") (pinfunction "VDD_SPI_BUF_F24") (pintype "power_in"))
    )
    (net (code "19") (name "Net-(IC1F-DVDD_SXR)") (class "Default")
      (node (ref "C56") (pin "1") (pinfunction "1_1") (pintype "passive"))
      (node (ref "FR4") (pin "1") (pinfunction "1_1") (pintype "passive"))
      (node (ref "IC1") (pin "AL21") (pinfunction "DVDD_SXR_AL21") (pintype "power_in"))
    )
    (net (code "20") (name "Net-(IC1F-DVDD_SXT)") (class "Default")
      (node (ref "C55") (pin "2") (pinfunction "2_2") (pintype "passive"))
      (node (ref "FR5") (pin "1") (pinfunction "1_1") (pintype "passive"))
      (node (ref "IC1") (pin "M4") (pinfunction "DVDD_SXT_M4") (pintype "power_in"))
    )
    (net (code "21") (name "Net-(IC1F-VDD12O_VCO_SXT)") (class "Default")
      (node (ref "C78") (pin "2") (pinfunction "2_2") (pintype "passive"))
      (node (ref "FR7") (pin "1") (pinfunction "1_1") (pintype "passive"))
      (node (ref "IC1") (pin "J5") (pinfunction "VDD12O_VCO_SXT_J5") (pintype "power_in"))
      (node (ref "IC1") (pin "K6") (pinfunction "VDD12_VCO_SXT_K6") (pintype "power_in"))
    )
    (net (code "22") (name "Net-(IC1F-VDD12_LNA_RFE)") (class "Default")
      (node (ref "C75") (pin "1") (pinfunction "1_1") (pintype "passive"))
      (node (ref "FR11") (pin "1") (pinfunction "1_1") (pintype "passive"))
      (node (ref "IC1") (pin "AG5") (pinfunction "VDD12_LNA_RFE_AG5") (pintype "power_in"))
    )
    (net (code "23") (name "Net-(IC1F-VDD12_RXBUF)") (class "Default")
      (node (ref "C71") (pin "1") (pinfunction "1_1") (pintype "passive"))
      (node (ref "IC1") (pin "AP26") (pinfunction "VDD12_RXBUF_AP26") (pintype "power_in"))
      (node (ref "R67") (pin "1") (pinfunction "1_1") (pintype "passive"))
    )
    (net (code "24") (name "Net-(IC1F-VDD12_TIA_RFE)") (class "Default")
      (node (ref "C76") (pin "2") (pinfunction "2_2") (pintype "passive"))
      (node (ref "FR10") (pin "1") (pinfunction "1_1") (pintype "passive"))
      (node (ref "IC1") (pin "AD6") (pinfunction "VDD12_TIA_RFE_AD6") (pintype "power_in"))
    )
    (net (code "25") (name "Net-(IC1F-VDD12_TXBUF)") (class "Default")
      (node (ref "C63") (pin "1") (pinfunction "1_1") (pintype "passive"))
      (node (ref "IC1") (pin "G5") (pinfunction "VDD12_TXBUF_G5") (pintype "power_in"))
      (node (ref "R66") (pin "1") (pinfunction "1_1") (pintype "passive"))
    )
    (net (code "26") (name "Net-(IC1F-VDD12_VCO_SXR)") (class "Default")
      (node (ref "C72") (pin "1") (pinfunction "1_1") (pintype "passive"))
      (node (ref "FR14") (pin "1") (pinfunction "1_1") (pintype "passive"))
      (node (ref "IC1") (pin "AN23") (pinfunction "VDD12_VCO_SXR_AN23") (pintype "power_in"))
    )
    (net (code "27") (name "Net-(IC1F-VDD14_LNA_RFE)") (class "Default")
      (node (ref "C83") (pin "1") (pinfunction "1_1") (pintype "passive"))
      (node (ref "C84") (pin "1") (pinfunction "1_1") (pintype "passive"))
      (node (ref "C85") (pin "1") (pinfunction "1_1") (pintype "passive"))
      (node (ref "FR23") (pin "1") (pinfunction "1_1") (pintype "passive"))
      (node (ref "IC1") (pin "AD4") (pinfunction "VDD14_RBB_AD4") (pintype "power_in"))
      (node (ref "IC1") (pin "AF2") (pinfunction "VDD14_TIA_RFE_AF2") (pintype "power_in"))
      (node (ref "IC1") (pin "AF6") (pinfunction "VDD14_LNA_RFE_AF6") (pintype "power_in"))
    )
    (net (code "28") (name "Net-(IC1F-VDD14_VCO_CGEN)") (class "Default")
      (node (ref "C81") (pin "1") (pinfunction "1_1") (pintype "passive"))
      (node (ref "C82") (pin "1") (pinfunction "1_1") (pintype "passive"))
      (node (ref "FR24") (pin "1") (pinfunction "1_1") (pintype "passive"))
      (node (ref "IC1") (pin "C21") (pinfunction "VDD14_VCO_CGEN_C21") (pintype "power_in"))
    )
    (net (code "29") (name "Net-(IC1F-VDDO_DIV_SXT)") (class "Default")
      (node (ref "C80") (pin "1") (pinfunction "1_1") (pintype "passive"))
      (node (ref "FR21") (pin "1") (pinfunction "1_1") (pintype "passive"))
      (node (ref "IC1") (pin "K2") (pinfunction "VDDO_DIV_SXT_K2") (pintype "power_in"))
      (node (ref "IC1") (pin "L5") (pinfunction "VDD_DIV_SXT_L5") (pintype "power_in"))
    )
    (net (code "30") (name "Net-(IC1F-VDDO_TLOBUF_TRF)") (class "Default")
      (node (ref "C65") (pin "1") (pinfunction "1_1") (pintype "passive"))
      (node (ref "FR20") (pin "1") (pinfunction "1_1") (pintype "passive"))
      (node (ref "IC1") (pin "D6") (pinfunction "VDDO_TLOBUF_TRF_D6") (pintype "power_in"))
      (node (ref "IC1") (pin "F8") (pinfunction "VDD_TLOBUF_TRF_F8") (pintype "power_in"))
    )
    (net (code "31") (name "Net-(IC1F-VDD_AFE)") (class "Default")
      (node (ref "C70") (pin "1") (pinfunction "1_1") (pintype "passive"))
      (node (ref "FR16") (pin "1") (pinfunction "1_1") (pintype "passive"))
      (node (ref "IC1") (pin "AJ25") (pinfunction "VDD_AFE_AJ25") (pintype "power_in"))
    )
    (net (code "32") (name "Net-(IC1F-VDD_CP_CGEN)") (class "Default")
      (node (ref "C69") (pin "2") (pinfunction "2_2") (pintype "passive"))
      (node (ref "FR17") (pin "1") (pinfunction "1_1") (pintype "passive"))
      (node (ref "IC1") (pin "F20") (pinfunction "VDD_CP_CGEN_F20") (pintype "power_in"))
    )
    (net (code "33") (name "Net-(IC1F-VDD_CP_SXR)") (class "Default")
      (node (ref "C74") (pin "1") (pinfunction "1_1") (pintype "passive"))
      (node (ref "FR12") (pin "1") (pinfunction "1_1") (pintype "passive"))
      (node (ref "IC1") (pin "AL19") (pinfunction "VDD_CP_SXR_AL19") (pintype "power_in"))
    )
    (net (code "34") (name "Net-(IC1F-VDD_CP_SXT)") (class "Default")
      (node (ref "C77") (pin "1") (pinfunction "1_1") (pintype "passive"))
      (node (ref "FR8") (pin "1") (pinfunction "1_1") (pintype "passive"))
      (node (ref "IC1") (pin "J3") (pinfunction "VDD_CP_SXT_J3") (pintype "power_in"))
    )
    (net (code "35") (name "Net-(IC1F-VDD_DIV_CGEN)") (class "Default")
      (node (ref "C67") (pin "1") (pinfunction "1_1") (pintype "passive"))
      (node (ref "C68") (pin "1") (pinfunction "1_1") (pintype "passive"))
      (node (ref "FR18") (pin "1") (pinfunction "1_1") (pintype "passive"))
      (node (ref "IC1") (pin "E19") (pinfunction "VDD_DIV_CGEN_E19") (pintype "power_in"))
    )
    (net (code "36") (name "Net-(IC1F-VDD_DIV_SXR)") (class "Default")
      (node (ref "C73") (pin "1") (pinfunction "1_1") (pintype "passive"))
      (node (ref "FR13") (pin "1") (pinfunction "1_1") (pintype "passive"))
      (node (ref "IC1") (pin "AM20") (pinfunction "VDD_DIV_SXR_AM20") (pintype "power_in"))
    )
    (net (code "37") (name "Net-(IC1F-VDD_MXLOBUF_RFE)") (class "Default")
      (node (ref "C86") (pin "1") (pinfunction "1_1") (pintype "passive"))
      (node (ref "FR22") (pin "1") (pinfunction "1_1") (pintype "passive"))
      (node (ref "IC1") (pin "AN17") (pinfunction "VDD_MXLOBUF_RFE_AN17") (pintype "power_in"))
    )
    (net (code "38") (name "Net-(IC1F-VDD_TBB)") (class "Default")
      (node (ref "C64") (pin "1") (pinfunction "1_1") (pintype "passive"))
      (node (ref "FR51") (pin "1") (pinfunction "1_1") (pintype "passive"))
      (node (ref "FR9") (pin "1") (pinfunction "1_1") (pintype "passive"))
      (node (ref "IC1") (pin "P4") (pinfunction "VDD_TBB_P4") (pintype "power_in"))
    )
    (net (code "39") (name "Net-(IC1F-VDD_TPAD_TRF)") (class "Default")
      (node (ref "C66") (pin "1") (pinfunction "1_1") (pintype "passive"))
      (node (ref "FR19") (pin "1") (pinfunction "1_1") (pintype "passive"))
      (node (ref "IC1") (pin "B16") (pinfunction "VDD_TPAD_TRF_B16") (pintype "power_in"))
    )
    (net (code "40") (name "VCC1P4_LMS") (class "Default")
      (node (ref "FR21") (pin "2") (pinfunction "2_2") (pintype "passive"))
      (node (ref "FR22") (pin "2") (pinfunction "2_2") (pintype "passive"))
      (node (ref "FR23") (pin "2") (pinfunction "2_2") (pintype "passive"))
      (node (ref "FR24") (pin "2") (pinfunction "2_2") (pintype "passive"))
      (node (ref "FR9") (pin "2") (pinfunction "2_2") (pintype "passive"))
    )
    (net (code "41") (name "VCC1P8_LMS") (class "Default")
      (node (ref "FR25") (pin "2") (pinfunction "2_2") (pintype "passive"))
      (node (ref "FR26") (pin "1") (pinfunction "1_1") (pintype "passive"))
      (node (ref "FR27") (pin "1") (pinfunction "1_1") (pintype "passive"))
      (node (ref "FR28") (pin "2") (pinfunction "2_2") (pintype "passive"))
      (node (ref "FR29") (pin "2") (pinfunction "2_2") (pintype "passive"))
      (node (ref "FR30") (pin "2") (pinfunction "2_2") (pintype "passive"))
      (node (ref "FR31") (pin "2") (pinfunction "2_2") (pintype "passive"))
      (node (ref "FR32") (pin "2") (pinfunction "2_2") (pintype "passive"))
      (node (ref "R68") (pin "2") (pinfunction "2_2") (pintype "passive"))
      (node (ref "R70") (pin "2") (pinfunction "2_2") (pintype "passive"))
      (node (ref "R71") (pin "1") (pinfunction "1_1") (pintype "passive"))
    )
    (net (code "42") (name "VCC1P25_LMS") (class "Default")
      (node (ref "FR10") (pin "2") (pinfunction "2_2") (pintype "passive"))
      (node (ref "FR11") (pin "2") (pinfunction "2_2") (pintype "passive"))
      (node (ref "FR12") (pin "2") (pinfunction "2_2") (pintype "passive"))
      (node (ref "FR13") (pin "2") (pinfunction "2_2") (pintype "passive"))
      (node (ref "FR14") (pin "2") (pinfunction "2_2") (pintype "passive"))
      (node (ref "FR15") (pin "2") (pinfunction "2_2") (pintype "passive"))
      (node (ref "FR16") (pin "2") (pinfunction "2_2") (pintype "passive"))
      (node (ref "FR17") (pin "2") (pinfunction "2_2") (pintype "passive"))
      (node (ref "FR18") (pin "2") (pinfunction "2_2") (pintype "passive"))
      (node (ref "FR19") (pin "2") (pinfunction "2_2") (pintype "passive"))
      (node (ref "FR20") (pin "2") (pinfunction "2_2") (pintype "passive"))
      (node (ref "FR4") (pin "2") (pinfunction "2_2") (pintype "passive"))
      (node (ref "FR5") (pin "2") (pinfunction "2_2") (pintype "passive"))
      (node (ref "FR51") (pin "2") (pinfunction "2_2") (pintype "passive"))
      (node (ref "FR6") (pin "2") (pinfunction "2_2") (pintype "passive"))
      (node (ref "FR7") (pin "2") (pinfunction "2_2") (pintype "passive"))
      (node (ref "FR8") (pin "2") (pinfunction "2_2") (pintype "passive"))
      (node (ref "R65") (pin "1") (pinfunction "1_1") (pintype "passive"))
    )
    (net (code "43") (name "VDIO_LMS") (class "Default")
      (node (ref "R69") (pin "1") (pinfunction "1_1") (pintype "passive"))
    )
  )
)
